# Modulo-1B-TY.net
KiCad netlist of a schematic drawn in Altium Designer
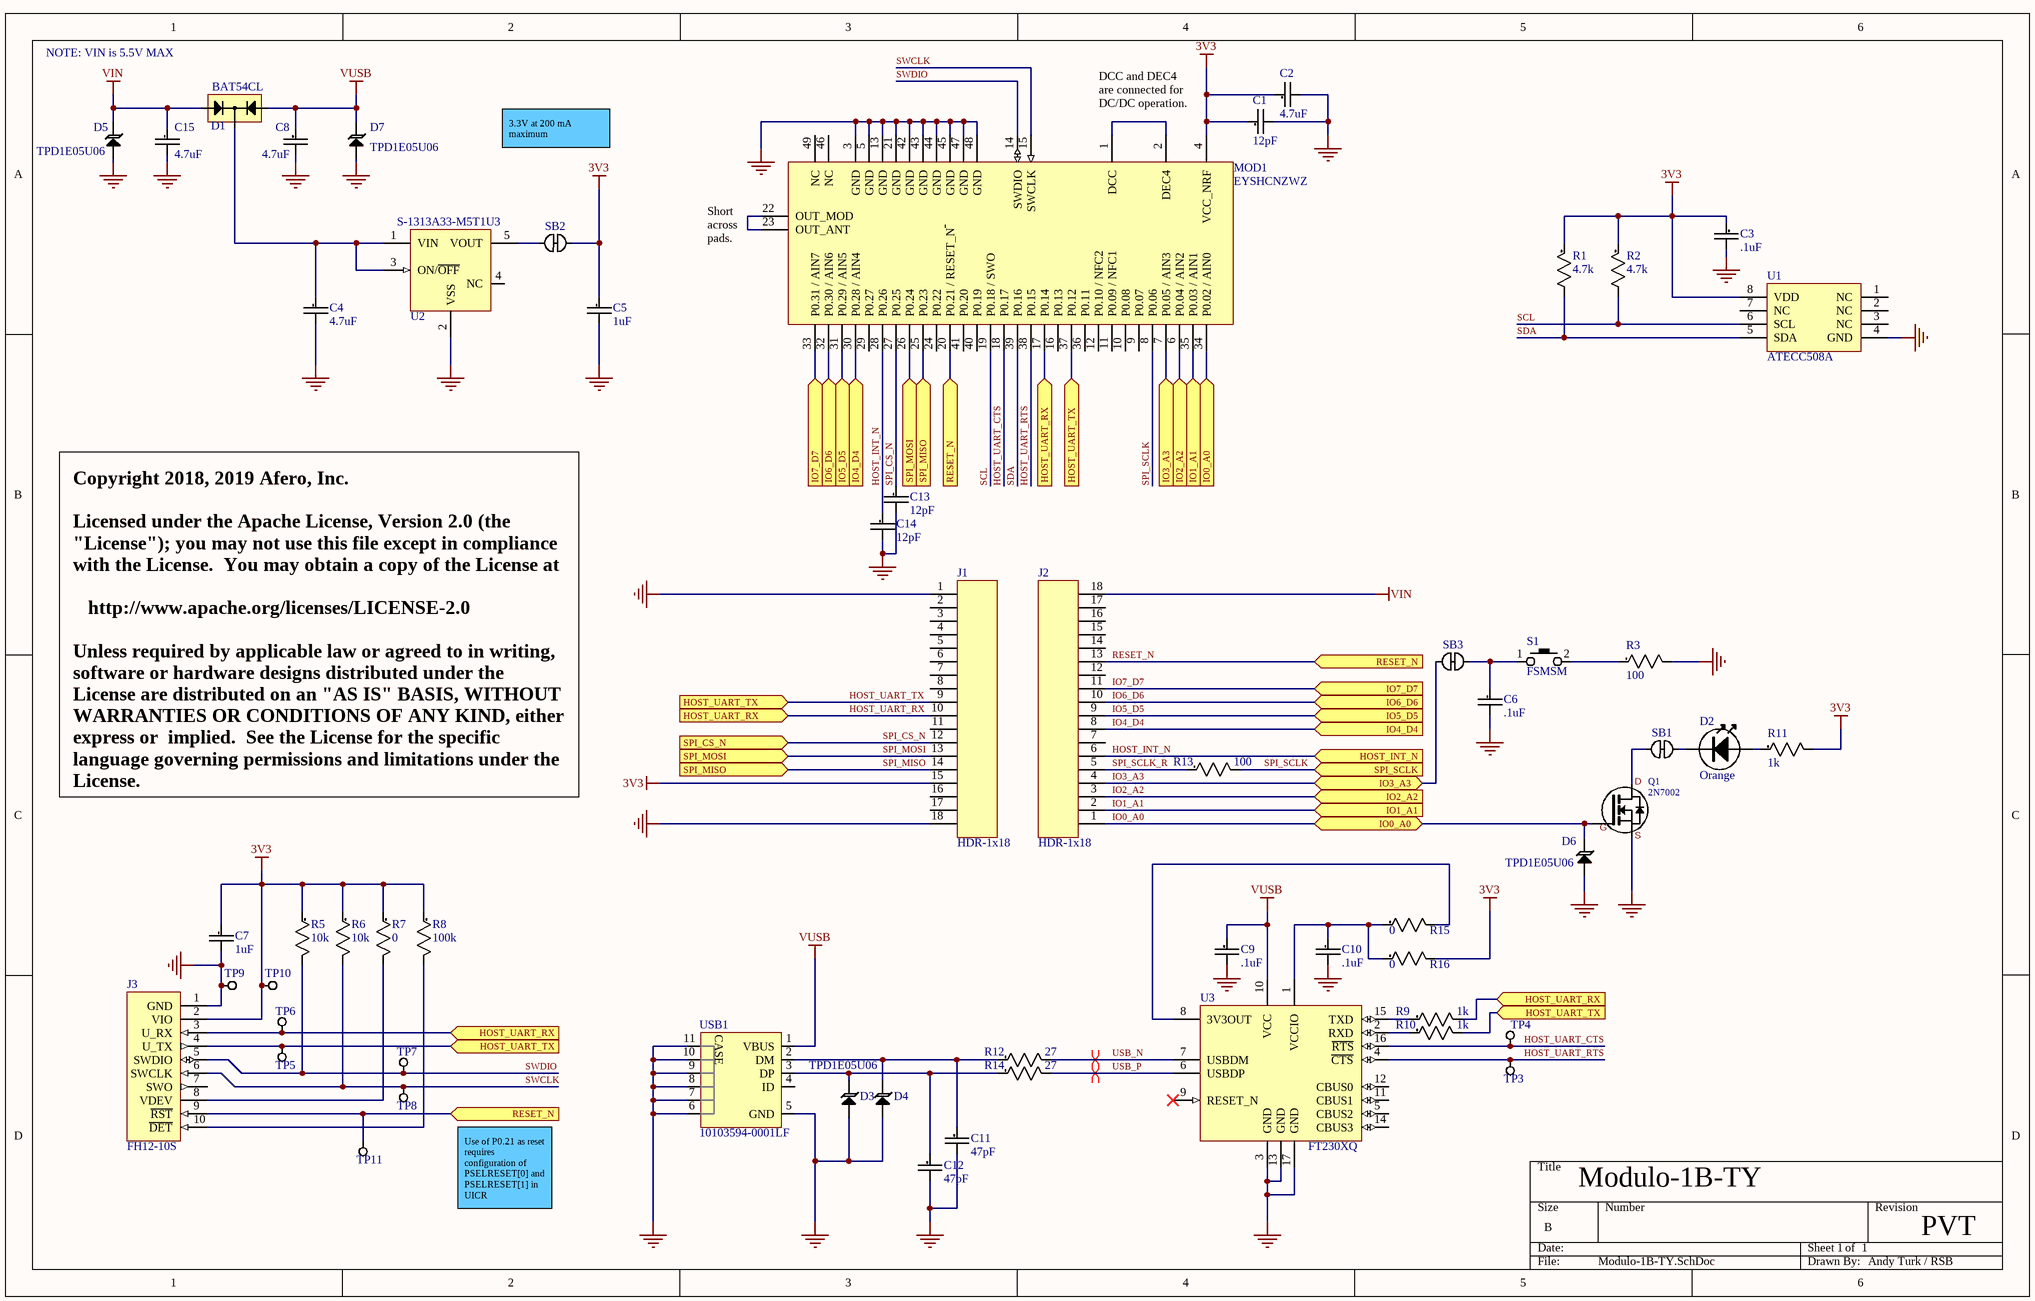
[diagram p0: Modulo-1B-TY.SchDoc]

(export (version "E")
  (design (tool "Eeschema 10.0.6"))
  (components
    (comp (ref "C1")
      (value "12pF")
      (footprint "0402C-GENERIC")
      (description "Capacitor, C0G")
      (fields
        (field (name "MANUFACTURER") "Murata")
        (field (name "MANUFACTURER PART NUMBER") "GJM1555C1H120FB01D")
      )
      (libsource (lib "Modulo-1B-TY") (part "0402C-12p"))
    )
    (comp (ref "C2")
      (value "4.7uF")
      (footprint "0603C-GENERIC")
      (description "Capacitor")
      (fields
        (field (name "MANUFACTURER") "Murata")
        (field (name "MANUFACTURER PART NUMBER") "GRM188R61C475KAAJD")
      )
      (libsource (lib "modulo-1b") (part "0603C-4u7"))
    )
    (comp (ref "C3")
      (value ".1uF")
      (footprint "0402C-GENERIC")
      (description "Capacitor, MLCC")
      (fields
        (field (name "MANUFACTURER") "Murata")
        (field (name "MANUFACTURER PART NUMBER") "GRM155R61H104KE19D")
      )
      (libsource (lib "modulo-1b") (part "0402C-100n"))
    )
    (comp (ref "C4")
      (value "4.7uF")
      (footprint "0603C-GENERIC")
      (description "Capacitor")
      (fields
        (field (name "MANUFACTURER") "Murata")
        (field (name "MANUFACTURER PART NUMBER") "GRM188R61C475KAAJD")
      )
      (libsource (lib "modulo-1b") (part "0603C-4u7"))
    )
    (comp (ref "C5")
      (value "1uF")
      (footprint "0402C-GENERIC")
      (description "Capacitor, MLCC")
      (fields
        (field (name "MANUFACTURER") "Murata Electronics")
        (field (name "MANUFACTURER PART NUMBER") "GRM155R60J105ME19J")
      )
      (libsource (lib "modulo-1b") (part "0402C-1u"))
    )
    (comp (ref "C6")
      (value ".1uF")
      (footprint "0402C-GENERIC")
      (description "Capacitor, MLCC")
      (fields
        (field (name "MANUFACTURER") "Murata")
        (field (name "MANUFACTURER PART NUMBER") "GRM155R61H104KE19D")
      )
      (libsource (lib "modulo-1b") (part "0402C-100n"))
    )
    (comp (ref "C7")
      (value "1uF")
      (footprint "0402C-GENERIC")
      (description "Capacitor, MLCC")
      (fields
        (field (name "MANUFACTURER") "Murata Electronics")
        (field (name "MANUFACTURER PART NUMBER") "GRM155R60J105ME19J")
      )
      (libsource (lib "modulo-1b") (part "0402C-1u"))
    )
    (comp (ref "C8")
      (value "4.7uF")
      (footprint "0603C-GENERIC")
      (description "Capacitor")
      (fields
        (field (name "MANUFACTURER") "Murata")
        (field (name "MANUFACTURER PART NUMBER") "GRM188R61C475KAAJD")
      )
      (libsource (lib "modulo-1b") (part "0603C-4u7"))
    )
    (comp (ref "C9")
      (value ".1uF")
      (footprint "0402C-GENERIC")
      (description "Capacitor, MLCC")
      (fields
        (field (name "MANUFACTURER") "Murata")
        (field (name "MANUFACTURER PART NUMBER") "GRM155R61H104KE19D")
      )
      (libsource (lib "modulo-1b") (part "0402C-100n"))
    )
    (comp (ref "C10")
      (value ".1uF")
      (footprint "0402C-GENERIC")
      (description "Capacitor, MLCC")
      (fields
        (field (name "MANUFACTURER") "Murata")
        (field (name "MANUFACTURER PART NUMBER") "GRM155R61H104KE19D")
      )
      (libsource (lib "modulo-1b") (part "0402C-100n"))
    )
    (comp (ref "C11")
      (value "47pF")
      (footprint "0402C-GENERIC")
      (description "Capacitor, C0G")
      (fields
        (field (name "MANUFACTURER") "Murata")
        (field (name "MANUFACTURER PART NUMBER") "GRM1555C1H470JZ01D")
      )
      (libsource (lib "modulo-1b") (part "0402C-47p"))
    )
    (comp (ref "C12")
      (value "47pF")
      (footprint "0402C-GENERIC")
      (description "Capacitor, C0G")
      (fields
        (field (name "MANUFACTURER") "Murata")
        (field (name "MANUFACTURER PART NUMBER") "GRM1555C1H470JZ01D")
      )
      (libsource (lib "modulo-1b") (part "0402C-47p"))
    )
    (comp (ref "C13")
      (value "12pF")
      (footprint "0402C-GENERIC")
      (description "Capacitor, C0G")
      (fields
        (field (name "MANUFACTURER") "Murata")
        (field (name "MANUFACTURER PART NUMBER") "GJM1555C1H120FB01D")
      )
      (libsource (lib "Modulo-1B-TY") (part "0402C-12p"))
    )
    (comp (ref "C14")
      (value "12pF")
      (footprint "0402C-GENERIC")
      (description "Capacitor, C0G")
      (fields
        (field (name "MANUFACTURER") "Murata")
        (field (name "MANUFACTURER PART NUMBER") "GJM1555C1H120FB01D")
      )
      (libsource (lib "Modulo-1B-TY") (part "0402C-12p"))
    )
    (comp (ref "C15")
      (value "4.7uF")
      (footprint "0603C-GENERIC")
      (description "Capacitor")
      (fields
        (field (name "MANUFACTURER") "Murata")
        (field (name "MANUFACTURER PART NUMBER") "GRM188R61C475KAAJD")
      )
      (libsource (lib "Modulo-1B-TY") (part "0603C-4u7"))
    )
    (comp (ref "D1")
      (value "BAT54CL")
      (footprint "SOT23")
      (description "Dual Common Cathode  Schottky  Diodes")
      (fields
        (field (name "MANUFACTURER") "ON Semiconductor")
        (field (name "MANUFACTURER PART NUMBER") "BAT54CLT1G")
      )
      (libsource (lib "modulo-1b") (part "BAT54CL"))
    )
    (comp (ref "D2")
      (value "Orange")
      (footprint "0603LED")
      (description "LED_0603")
      (fields
        (field (name "MANUFACTURER") "Vishay Lite-On")
        (field (name "MANUFACTURER PART NUMBER") "LTST-C190KAKT")
      )
      (libsource (lib "Modulo-1B-TY") (part "LED_0603"))
    )
    (comp (ref "D3")
      (value "TPD1E05U06")
      (footprint "SON70P100X45-2N")
      (description "TVS Diode")
      (fields
        (field (name "MANUFACTURER") "Texas Instruments")
        (field (name "MANUFACTURER PART NUMBER") "TPD1E05U06DPYR")
      )
      (libsource (lib "modulo-1b") (part "TPD1E05U06"))
    )
    (comp (ref "D4")
      (value "TPD1E05U06")
      (footprint "SON70P100X45-2N")
      (description "TVS Diode")
      (fields
        (field (name "MANUFACTURER") "Texas Instruments")
        (field (name "MANUFACTURER PART NUMBER") "TPD1E05U06DPYR")
      )
      (libsource (lib "modulo-1b") (part "TPD1E05U06"))
    )
    (comp (ref "D5")
      (value "TPD1E05U06")
      (footprint "SON70P100X45-2N")
      (description "TVS Diode")
      (fields
        (field (name "MANUFACTURER") "Texas Instruments")
        (field (name "MANUFACTURER PART NUMBER") "TPD1E05U06DPYR")
      )
      (libsource (lib "Modulo-1B-TY") (part "TPD1E05U06"))
    )
    (comp (ref "D6")
      (value "TPD1E05U06")
      (footprint "SON70P100X45-2N")
      (description "TVS Diode")
      (fields
        (field (name "MANUFACTURER") "Texas Instruments")
        (field (name "MANUFACTURER PART NUMBER") "TPD1E05U06DPYR")
      )
      (libsource (lib "Modulo-1B-TY") (part "TPD1E05U06"))
    )
    (comp (ref "D7")
      (value "TPD1E05U06")
      (footprint "SON70P100X45-2N")
      (description "TVS Diode")
      (fields
        (field (name "MANUFACTURER") "Texas Instruments")
        (field (name "MANUFACTURER PART NUMBER") "TPD1E05U06DPYR")
      )
      (libsource (lib "Modulo-1B-TY") (part "TPD1E05U06"))
    )
    (comp (ref "J1")
      (value "HDR-1x18")
      (footprint "HDR-1X18")
      (libsource (lib "modulo-1b") (part "HDR-1x18"))
    )
    (comp (ref "J2") (value "HDR-1x18") (footprint "HDR-1X18") (libsource (lib "") (part "HDR-1x18_1")))
    (comp (ref "J3")
      (value "FH12-10S")
      (description "Afero SAD connector")
      (fields
        (field (name "MANUFACTURER") "Hirose")
        (field (name "MANUFACTURER PART NUMBER") "FH12-10S-0.5SH(55)")
      )
      (libsource (lib "modulo-1b") (part "SAD-WIFI"))
    )
    (comp (ref "MOD1")
      (value "EYSHCNZWZ")
      (footprint "EYSHCNZWZ")
      (description "Bluetooth 5.0 Low Energy Module")
      (fields (field (name "MANUFACTURER") "Taiyo Yuden"))
      (libsource (lib "modulo-1b") (part "EYSHCNZWZ"))
    )
    (comp (ref "Q1")
      (value "2N7002")
      (footprint "SOT23")
      (description "MOSFET N-CH 60V 115mA SOT23")
      (fields (field (name "MANUFACTURER") "On Semiconductor"))
      (libsource (lib "Modulo-1B-TY") (part "Nch_MOSFET_2N7002"))
    )
    (comp (ref "R1")
      (value "4.7k")
      (footprint "0402R-GENERIC")
      (description "Resistor 4k7")
      (fields
        (field (name "MANUFACTURER") "Panasonic")
        (field (name "MANUFACTURER PART NUMBER") "ERJ-2GEJ472X")
      )
      (libsource (lib "modulo-1b") (part "0402R-4k7"))
    )
    (comp (ref "R2")
      (value "4.7k")
      (footprint "0402R-GENERIC")
      (description "Resistor 4k7")
      (fields
        (field (name "MANUFACTURER") "Panasonic")
        (field (name "MANUFACTURER PART NUMBER") "ERJ-2GEJ472X")
      )
      (libsource (lib "modulo-1b") (part "0402R-4k7"))
    )
    (comp (ref "R3")
      (value "100")
      (footprint "0402R-GENERIC")
      (description "Resistor 100R")
      (fields
        (field (name "MANUFACTURER") "Vishay Dale")
        (field (name "MANUFACTURER PART NUMBER") "CRCW0402100RFKED")
      )
      (libsource (lib "modulo-1b") (part "0402R-100R"))
    )
    (comp (ref "R5")
      (value "10k")
      (footprint "0402R-GENERIC")
      (description "Resistor 10k")
      (fields
        (field (name "MANUFACTURER") "Vishay Dale")
        (field (name "MANUFACTURER PART NUMBER") "CRCW040210K0JNED")
      )
      (libsource (lib "modulo-1b") (part "0402R-10k"))
    )
    (comp (ref "R6")
      (value "10k")
      (footprint "0402R-GENERIC")
      (description "Resistor 10k")
      (fields
        (field (name "MANUFACTURER") "Vishay Dale")
        (field (name "MANUFACTURER PART NUMBER") "CRCW040210K0JNED")
      )
      (libsource (lib "modulo-1b") (part "0402R-10k"))
    )
    (comp (ref "R7")
      (value "0")
      (footprint "0603R-generic")
      (description "Resistor 0R")
      (fields
        (field (name "MANUFACTURER") "Panasonic")
        (field (name "MANUFACTURER PART NUMBER") "ERJ-3GEY0R00V")
      )
      (libsource (lib "modulo-1b") (part "0603R-0R0"))
    )
    (comp (ref "R8")
      (value "100k")
      (footprint "0402R-GENERIC")
      (description "Resistor 100k")
      (fields
        (field (name "MANUFACTURER") "Panasonic")
        (field (name "MANUFACTURER PART NUMBER") "ERJ-2GEJ104X")
      )
      (libsource (lib "modulo-1b") (part "0402R-100k"))
    )
    (comp (ref "R9")
      (value "1k")
      (footprint "0402R-GENERIC")
      (description "Resistor 1k")
      (fields
        (field (name "MANUFACTURER") "Yageo")
        (field (name "MANUFACTURER PART NUMBER") "RT0402-FRE071KL")
      )
      (libsource (lib "modulo-1b") (part "0402R-1k"))
    )
    (comp (ref "R10")
      (value "1k")
      (footprint "0402R-GENERIC")
      (description "Resistor 1k")
      (fields
        (field (name "MANUFACTURER") "Yageo")
        (field (name "MANUFACTURER PART NUMBER") "RT0402-FRE071KL")
      )
      (libsource (lib "modulo-1b") (part "0402R-1k"))
    )
    (comp (ref "R11")
      (value "1k")
      (footprint "0402R-GENERIC")
      (description "Resistor 1k")
      (fields
        (field (name "MANUFACTURER") "Yageo")
        (field (name "MANUFACTURER PART NUMBER") "RT0402-FRE071KL")
      )
      (libsource (lib "Modulo-1B-TY") (part "0402R-1k"))
    )
    (comp (ref "R12")
      (value "27")
      (footprint "0402R-GENERIC")
      (description "Resistor 27R")
      (fields
        (field (name "MANUFACTURER") "Vishay")
        (field (name "MANUFACTURER PART NUMBER") "CRCW040227R0FKED")
      )
      (libsource (lib "modulo-1b") (part "0402R-27R"))
    )
    (comp (ref "R13")
      (value "100")
      (footprint "0402R-GENERIC")
      (description "Resistor 100R")
      (fields
        (field (name "MANUFACTURER") "Vishay Dale")
        (field (name "MANUFACTURER PART NUMBER") "CRCW0402100RFKED")
      )
      (libsource (lib "Modulo-1B-TY") (part "0402R-100R"))
    )
    (comp (ref "R14")
      (value "27")
      (footprint "0402R-GENERIC")
      (description "Resistor 27R")
      (fields
        (field (name "MANUFACTURER") "Vishay")
        (field (name "MANUFACTURER PART NUMBER") "CRCW040227R0FKED")
      )
      (libsource (lib "modulo-1b") (part "0402R-27R"))
    )
    (comp (ref "R15")
      (value "0")
      (footprint "0402R-GENERIC")
      (description "Resistor 0R")
      (fields
        (field (name "MANUFACTURER") "Yageo")
        (field (name "MANUFACTURER PART NUMBER") "RC0402FR-070RL")
      )
      (libsource (lib "Modulo-1B-TY") (part "0402R-0R0"))
    )
    (comp (ref "R16")
      (value "0")
      (footprint "0402R-GENERIC")
      (description "Resistor 0R")
      (fields
        (field (name "MANUFACTURER") "Yageo")
        (field (name "MANUFACTURER PART NUMBER") "RC0402FR-070RL")
      )
      (libsource (lib "Modulo-1B-TY") (part "0402R-0R0"))
    )
    (comp (ref "S1")
      (value "FSMSM")
      (footprint "FSMSM")
      (description "SMD Tact Switch")
      (fields (field (name "MANUFACTURER") "TE Connectivity Alcoswitch"))
      (libsource (lib "modulo-1b") (part "FSMSM"))
    )
    (comp (ref "SB1")
      (value "Solderbridge")
      (footprint "SBNC")
      (description "Solderbridge, Normally Closed")
      (fields
        (field (name "PART NUMBER") "Solderbridge Shorted")
        (field (name "PUBLISHER") "Nordic Semiconductor")
      )
      (libsource (lib "modulo-1c") (part "SBNC"))
    )
    (comp (ref "SB2")
      (value "Solderbridge")
      (footprint "SBNC")
      (description "Solderbridge, Normally Closed")
      (fields
        (field (name "PART NUMBER") "Solderbridge Shorted")
        (field (name "PUBLISHER") "Nordic Semiconductor")
      )
      (libsource (lib "modulo-1c") (part "SBNC"))
    )
    (comp (ref "SB3")
      (value "Solderbridge")
      (footprint "SBNC")
      (description "Solderbridge, Normally Closed")
      (fields
        (field (name "PART NUMBER") "Solderbridge Shorted")
        (field (name "PUBLISHER") "Nordic Semiconductor")
      )
      (libsource (lib "modulo-1c") (part "SBNC"))
    )
    (comp (ref "TP3")
      (value "TP1MM")
      (footprint "TP1MM")
      (description "1mm Test Point")
      (libsource (lib "modulo-1b") (part "TP1MM"))
    )
    (comp (ref "TP4")
      (value "TP1MM")
      (footprint "TP1MM")
      (description "1mm Test Point")
      (libsource (lib "modulo-1b") (part "TP1MM"))
    )
    (comp (ref "TP5")
      (value "TP1MM")
      (footprint "TP1MM")
      (description "1mm Test Point")
      (libsource (lib "modulo-1b") (part "TP1MM"))
    )
    (comp (ref "TP6")
      (value "TP1MM")
      (footprint "TP1MM")
      (description "1mm Test Point")
      (libsource (lib "modulo-1b") (part "TP1MM"))
    )
    (comp (ref "TP7")
      (value "TP1MM")
      (footprint "TP1MM")
      (description "1mm Test Point")
      (libsource (lib "modulo-1b") (part "TP1MM"))
    )
    (comp (ref "TP8")
      (value "TP1MM")
      (footprint "TP1MM")
      (description "1mm Test Point")
      (libsource (lib "modulo-1b") (part "TP1MM"))
    )
    (comp (ref "TP9")
      (value "TP1MM")
      (footprint "TP1MM")
      (description "1mm Test Point")
      (libsource (lib "modulo-1b") (part "TP1MM"))
    )
    (comp (ref "TP10")
      (value "TP1MM")
      (footprint "TP1MM")
      (description "1mm Test Point")
      (libsource (lib "modulo-1b") (part "TP1MM"))
    )
    (comp (ref "TP11")
      (value "TP1MM")
      (footprint "TP1MM")
      (description "1mm Test Point")
      (libsource (lib "modulo-1b") (part "TP1MM"))
    )
    (comp (ref "U1")
      (value "ATECC508A")
      (footprint "SON50P300X60-8N")
      (description "Afero Custom CryptoAuthentication Device")
      (fields
        (field (name "MANUFACTURER") "Microchip / Atmel")
        (field (name "MANUFACTURER PART NUMBER") "ATECC508A-MAHCZ-T")
      )
      (libsource (lib "modulo-1b") (part "ATECC508A"))
    )
    (comp (ref "U2")
      (value "S-1313A33-M5T1U3")
      (footprint "SOT95P275X130-5N")
      (description "Low Current Consumption LDO")
      (fields (field (name "MANUFACTURER") "Seiko"))
      (libsource (lib "modulo-1b") (part "S-1313A33-M5T1U3"))
    )
    (comp (ref "U3")
      (value "FT230XQ")
      (footprint "VQFN65P400X400X90-16N")
      (description "USB to UART Bridge")
      (fields (field (name "MANUFACTURER") "FTDI") (field (name "MANUFACTURER PART NUMBER") "FT230XQ-R"))
      (libsource (lib "modulo-1b") (part "FT230XQ"))
    )
    (comp (ref "USB1")
      (value "10103594-0001LF")
      (footprint "10103594-0001LF")
      (description "MICRO USB B")
      (fields (field (name "MANUFACTURER") "Amphenol FCI"))
      (libsource (lib "modulo-1b") (part "10103594-0001LF"))
    )
  )
  (nets
    (net (code "1") (name "/HOST_INT_N") (class "Default")
      (node (ref "C14") (pin "1") (pintype "passive"))
      (node (ref "J2") (pin "6") (pinfunction "6_6") (pintype "power_in"))
      (node (ref "MOD1") (pin "28") (pinfunction "P0.26_28") (pintype "passive"))
    )
    (net (code "2") (name "/HOST_UART_CTS") (class "Default")
      (node (ref "MOD1") (pin "18") (pinfunction "P0.17_18") (pintype "passive"))
      (node (ref "TP4") (pin "1") (pinfunction "1_1") (pintype "passive"))
      (node (ref "U3") (pin "16") (pinfunction "~{RTS}_16") (pintype "bidirectional"))
    )
    (net (code "3") (name "/HOST_UART_RTS") (class "Default")
      (node (ref "MOD1") (pin "38") (pinfunction "P0.15_38") (pintype "passive"))
      (node (ref "TP3") (pin "1") (pinfunction "1_1") (pintype "passive"))
      (node (ref "U3") (pin "4") (pinfunction "~{CTS}_4") (pintype "bidirectional"))
    )
    (net (code "4") (name "/HOST_UART_RX") (class "Default")
      (node (ref "J1") (pin "10") (pinfunction "10_10") (pintype "passive"))
      (node (ref "J3") (pin "3") (pinfunction "U_RX_3") (pintype "input"))
      (node (ref "MOD1") (pin "17") (pinfunction "P0.14_17") (pintype "passive"))
      (node (ref "R9") (pin "2") (pinfunction "2_2") (pintype "passive"))
      (node (ref "TP6") (pin "1") (pinfunction "1_1") (pintype "passive"))
    )
    (net (code "5") (name "/HOST_UART_TX") (class "Default")
      (node (ref "J1") (pin "9") (pinfunction "9_9") (pintype "passive"))
      (node (ref "J3") (pin "4") (pinfunction "U_TX_4") (pintype "output"))
      (node (ref "MOD1") (pin "37") (pinfunction "P0.12_37") (pintype "passive"))
      (node (ref "R10") (pin "2") (pinfunction "2_2") (pintype "passive"))
      (node (ref "TP5") (pin "1") (pinfunction "1_1") (pintype "passive"))
    )
    (net (code "6") (name "/IO0_A0") (class "Default")
      (node (ref "D6") (pin "1") (pinfunction "I/O_1") (pintype "passive"))
      (node (ref "J2") (pin "1") (pinfunction "1_1") (pintype "power_in"))
      (node (ref "MOD1") (pin "34") (pinfunction "P0.02_/_AIN0_34") (pintype "passive"))
      (node (ref "Q1") (pin "1") (pinfunction "G_1") (pintype "passive"))
    )
    (net (code "7") (name "/IO1_A1") (class "Default")
      (node (ref "J2") (pin "2") (pinfunction "2_2") (pintype "power_in"))
      (node (ref "MOD1") (pin "35") (pinfunction "P0.03_/_AIN1_35") (pintype "passive"))
    )
    (net (code "8") (name "/IO2_A2") (class "Default")
      (node (ref "J2") (pin "3") (pinfunction "3_3") (pintype "power_in"))
      (node (ref "MOD1") (pin "6") (pinfunction "P0.04_/_AIN2_6") (pintype "passive"))
    )
    (net (code "9") (name "/IO3_A3") (class "Default")
      (node (ref "J2") (pin "4") (pinfunction "4_4") (pintype "power_in"))
      (node (ref "MOD1") (pin "7") (pinfunction "P0.05_/_AIN3_7") (pintype "passive"))
      (node (ref "SB3") (pin "1") (pinfunction "0_1") (pintype "passive"))
    )
    (net (code "10") (name "/IO4_D4") (class "Default")
      (node (ref "J2") (pin "8") (pinfunction "8_8") (pintype "power_in"))
      (node (ref "MOD1") (pin "30") (pinfunction "P0.28_/_AIN4_30") (pintype "passive"))
    )
    (net (code "11") (name "/IO5_D5") (class "Default")
      (node (ref "J2") (pin "9") (pinfunction "9_9") (pintype "power_in"))
      (node (ref "MOD1") (pin "31") (pinfunction "P0.29_/_AIN5_31") (pintype "passive"))
    )
    (net (code "12") (name "/IO6_D6") (class "Default")
      (node (ref "J2") (pin "10") (pinfunction "10_10") (pintype "power_in"))
      (node (ref "MOD1") (pin "32") (pinfunction "P0.30_/_AIN6_32") (pintype "passive"))
    )
    (net (code "13") (name "/IO7_D7") (class "Default")
      (node (ref "J2") (pin "11") (pinfunction "11_11") (pintype "power_in"))
      (node (ref "MOD1") (pin "33") (pinfunction "P0.31_/_AIN7_33") (pintype "passive"))
    )
    (net (code "14") (name "/RESET_N") (class "Default")
      (node (ref "J2") (pin "13") (pinfunction "13_13") (pintype "power_in"))
      (node (ref "J3") (pin "9") (pinfunction "~{RST}_9") (pintype "input"))
      (node (ref "MOD1") (pin "20") (pinfunction "P0.21_/_RESET_N~{_}_20") (pintype "passive"))
      (node (ref "TP11") (pin "1") (pinfunction "1_1") (pintype "passive"))
    )
    (net (code "15") (name "/SCL") (class "Default")
      (node (ref "MOD1") (pin "19") (pinfunction "P0.18_/_SWO_19") (pintype "passive"))
      (node (ref "R2") (pin "2") (pinfunction "2_2") (pintype "passive"))
      (node (ref "U1") (pin "6") (pinfunction "SCL_6") (pintype "passive"))
    )
    (net (code "16") (name "/SDA") (class "Default")
      (node (ref "MOD1") (pin "39") (pinfunction "P0.16_39") (pintype "passive"))
      (node (ref "R1") (pin "2") (pinfunction "2_2") (pintype "passive"))
      (node (ref "U1") (pin "5") (pinfunction "SDA_5") (pintype "passive"))
    )
    (net (code "17") (name "/SPI_CS_N") (class "Default")
      (node (ref "C13") (pin "1") (pintype "passive"))
      (node (ref "J1") (pin "12") (pinfunction "12_12") (pintype "passive"))
      (node (ref "MOD1") (pin "27") (pinfunction "P0.25_27") (pintype "passive"))
    )
    (net (code "18") (name "/SPI_MISO") (class "Default")
      (node (ref "J1") (pin "14") (pinfunction "14_14") (pintype "passive"))
      (node (ref "MOD1") (pin "25") (pinfunction "P0.23_25") (pintype "passive"))
    )
    (net (code "19") (name "/SPI_MOSI") (class "Default")
      (node (ref "J1") (pin "13") (pinfunction "13_13") (pintype "passive"))
      (node (ref "MOD1") (pin "26") (pinfunction "P0.24_26") (pintype "passive"))
    )
    (net (code "20") (name "/SPI_SCLK") (class "Default")
      (node (ref "MOD1") (pin "8") (pinfunction "P0.06_8") (pintype "passive"))
      (node (ref "R13") (pin "2") (pinfunction "2_2") (pintype "passive"))
    )
    (net (code "21") (name "/SPI_SCLK_R") (class "Default")
      (node (ref "J2") (pin "5") (pinfunction "5_5") (pintype "power_in"))
      (node (ref "R13") (pin "1") (pinfunction "1_1") (pintype "passive"))
    )
    (net (code "22") (name "/SWCLK") (class "Default")
      (node (ref "J3") (pin "6") (pinfunction "SWCLK_6") (pintype "input"))
      (node (ref "MOD1") (pin "15") (pinfunction "SWCLK_15") (pintype "input"))
      (node (ref "R6") (pin "2") (pinfunction "2_2") (pintype "passive"))
      (node (ref "TP8") (pin "1") (pinfunction "1_1") (pintype "passive"))
    )
    (net (code "23") (name "/SWDIO") (class "Default")
      (node (ref "J3") (pin "5") (pinfunction "SWDIO_5") (pintype "bidirectional"))
      (node (ref "MOD1") (pin "14") (pinfunction "SWDIO_14") (pintype "bidirectional"))
      (node (ref "R5") (pin "2") (pinfunction "2_2") (pintype "passive"))
      (node (ref "TP7") (pin "1") (pinfunction "1_1") (pintype "passive"))
    )
    (net (code "24") (name "/USB_N") (class "Default")
      (node (ref "R12") (pin "2") (pinfunction "2_2") (pintype "passive"))
      (node (ref "U3") (pin "7") (pinfunction "USBDM_7") (pintype "passive"))
    )
    (net (code "25") (name "/USB_P") (class "Default")
      (node (ref "R14") (pin "2") (pinfunction "2_2") (pintype "passive"))
      (node (ref "U3") (pin "6") (pinfunction "USBDP_6") (pintype "passive"))
    )
    (net (code "26") (name "3V3") (class "Default")
      (node (ref "C1") (pin "1") (pintype "passive"))
      (node (ref "C2") (pin "1") (pintype "passive"))
      (node (ref "C3") (pin "1") (pintype "passive"))
      (node (ref "C5") (pin "1") (pintype "passive"))
      (node (ref "C7") (pin "1") (pintype "passive"))
      (node (ref "J1") (pin "15") (pinfunction "15_15") (pintype "passive"))
      (node (ref "J3") (pin "2") (pinfunction "VIO_2") (pintype "power_in"))
      (node (ref "MOD1") (pin "4") (pinfunction "VCC_NRF_4") (pintype "power_in"))
      (node (ref "R1") (pin "1") (pinfunction "1_1") (pintype "passive"))
      (node (ref "R11") (pin "2") (pinfunction "2_2") (pintype "passive"))
      (node (ref "R16") (pin "2") (pinfunction "2_2") (pintype "passive"))
      (node (ref "R2") (pin "1") (pinfunction "1_1") (pintype "passive"))
      (node (ref "R5") (pin "1") (pinfunction "1_1") (pintype "passive"))
      (node (ref "R6") (pin "1") (pinfunction "1_1") (pintype "passive"))
      (node (ref "R7") (pin "1") (pinfunction "1_1") (pintype "passive"))
      (node (ref "R8") (pin "1") (pinfunction "1_1") (pintype "passive"))
      (node (ref "SB2") (pin "2") (pinfunction "1_2") (pintype "passive"))
      (node (ref "TP10") (pin "1") (pinfunction "1_1") (pintype "passive"))
      (node (ref "U1") (pin "8") (pinfunction "VDD_8") (pintype "power_in"))
    )
    (net (code "27") (name "GND") (class "Default")
      (node (ref "C1") (pin "2") (pintype "passive"))
      (node (ref "C10") (pin "2") (pintype "passive"))
      (node (ref "C11") (pin "2") (pintype "passive"))
      (node (ref "C12") (pin "2") (pintype "passive"))
      (node (ref "C13") (pin "2") (pintype "passive"))
      (node (ref "C14") (pin "2") (pintype "passive"))
      (node (ref "C15") (pin "2") (pintype "passive"))
      (node (ref "C2") (pin "2") (pintype "passive"))
      (node (ref "C3") (pin "2") (pintype "passive"))
      (node (ref "C4") (pin "2") (pintype "passive"))
      (node (ref "C5") (pin "2") (pintype "passive"))
      (node (ref "C6") (pin "2") (pintype "passive"))
      (node (ref "C7") (pin "2") (pintype "passive"))
      (node (ref "C8") (pin "2") (pintype "passive"))
      (node (ref "C9") (pin "2") (pintype "passive"))
      (node (ref "D3") (pin "2") (pinfunction "GND_2") (pintype "passive"))
      (node (ref "D4") (pin "2") (pinfunction "GND_2") (pintype "passive"))
      (node (ref "D5") (pin "2") (pinfunction "GND_2") (pintype "passive"))
      (node (ref "D6") (pin "2") (pinfunction "GND_2") (pintype "passive"))
      (node (ref "D7") (pin "2") (pinfunction "GND_2") (pintype "passive"))
      (node (ref "J1") (pin "1") (pinfunction "1_1") (pintype "passive"))
      (node (ref "J1") (pin "18") (pinfunction "18_18") (pintype "passive"))
      (node (ref "J3") (pin "1") (pinfunction "GND_1") (pintype "power_in"))
      (node (ref "MOD1") (pin "13") (pinfunction "GND_13") (pintype "power_in"))
      (node (ref "MOD1") (pin "21") (pinfunction "GND_21") (pintype "power_in"))
      (node (ref "MOD1") (pin "3") (pinfunction "GND_3") (pintype "power_in"))
      (node (ref "MOD1") (pin "42") (pinfunction "GND_42") (pintype "power_in"))
      (node (ref "MOD1") (pin "43") (pinfunction "GND_43") (pintype "power_in"))
      (node (ref "MOD1") (pin "44") (pinfunction "GND_44") (pintype "power_in"))
      (node (ref "MOD1") (pin "45") (pinfunction "GND_45") (pintype "power_in"))
      (node (ref "MOD1") (pin "47") (pinfunction "GND_47") (pintype "power_in"))
      (node (ref "MOD1") (pin "48") (pinfunction "GND_48") (pintype "power_in"))
      (node (ref "MOD1") (pin "5") (pinfunction "GND_5") (pintype "power_in"))
      (node (ref "Q1") (pin "2") (pinfunction "S_2") (pintype "passive"))
      (node (ref "R3") (pin "2") (pinfunction "2_2") (pintype "passive"))
      (node (ref "TP9") (pin "1") (pinfunction "1_1") (pintype "passive"))
      (node (ref "U1") (pin "4") (pinfunction "GND_4") (pintype "power_in"))
      (node (ref "U2") (pin "2") (pinfunction "VSS_2") (pintype "power_in"))
      (node (ref "U3") (pin "13") (pinfunction "GND_13") (pintype "power_in"))
      (node (ref "U3") (pin "17") (pinfunction "GND_17") (pintype "power_in"))
      (node (ref "U3") (pin "3") (pinfunction "GND_3") (pintype "power_in"))
      (node (ref "USB1") (pin "10") (pinfunction "CASE_10") (pintype "passive"))
      (node (ref "USB1") (pin "11") (pinfunction "CASE_11") (pintype "passive"))
      (node (ref "USB1") (pin "5") (pinfunction "GND_5") (pintype "passive"))
      (node (ref "USB1") (pin "6") (pinfunction "CASE_6") (pintype "passive"))
      (node (ref "USB1") (pin "7") (pinfunction "CASE_7") (pintype "passive"))
      (node (ref "USB1") (pin "8") (pinfunction "CASE_8") (pintype "passive"))
      (node (ref "USB1") (pin "9") (pinfunction "CASE_9") (pintype "passive"))
    )
    (net (code "28") (name "Net-(D2-PadA)") (class "Default")
      (node (ref "D2") (pin "A") (pintype "passive"))
      (node (ref "R11") (pin "1") (pinfunction "1_1") (pintype "passive"))
    )
    (net (code "29") (name "Net-(D3-I{slash}O)") (class "Default")
      (node (ref "C12") (pin "1") (pintype "passive"))
      (node (ref "D3") (pin "1") (pinfunction "I/O_1") (pintype "passive"))
      (node (ref "R14") (pin "1") (pinfunction "1_1") (pintype "passive"))
      (node (ref "USB1") (pin "3") (pinfunction "DP_3") (pintype "passive"))
    )
    (net (code "30") (name "Net-(D4-I{slash}O)") (class "Default")
      (node (ref "C11") (pin "1") (pintype "passive"))
      (node (ref "D4") (pin "1") (pinfunction "I/O_1") (pintype "passive"))
      (node (ref "R12") (pin "1") (pinfunction "1_1") (pintype "passive"))
      (node (ref "USB1") (pin "2") (pinfunction "DM_2") (pintype "passive"))
    )
    (net (code "31") (name "Net-(J3-VDEV)") (class "Default")
      (node (ref "J3") (pin "8") (pinfunction "VDEV_8") (pintype "power_in"))
      (node (ref "R7") (pin "2") (pinfunction "2_2") (pintype "passive"))
    )
    (net (code "32") (name "Net-(J3-~{DET})") (class "Default")
      (node (ref "J3") (pin "10") (pinfunction "~{DET}_10") (pintype "input"))
      (node (ref "R8") (pin "2") (pinfunction "2_2") (pintype "passive"))
    )
    (net (code "33") (name "Net-(MOD1-DCC)") (class "Default")
      (node (ref "MOD1") (pin "1") (pinfunction "DCC_1") (pintype "passive"))
      (node (ref "MOD1") (pin "2") (pinfunction "DEC4_2") (pintype "passive"))
    )
    (net (code "34") (name "Net-(MOD1-OUT_ANT)") (class "Default")
      (node (ref "MOD1") (pin "22") (pinfunction "OUT_MOD_22") (pintype "passive"))
      (node (ref "MOD1") (pin "23") (pinfunction "OUT_ANT_23") (pintype "passive"))
    )
    (net (code "35") (name "Net-(Q1-D)") (class "Default")
      (node (ref "Q1") (pin "3") (pinfunction "D_3") (pintype "passive"))
      (node (ref "SB1") (pin "1") (pinfunction "0_1") (pintype "passive"))
    )
    (net (code "36") (name "Net-(R3-Pad1)") (class "Default")
      (node (ref "R3") (pin "1") (pinfunction "1_1") (pintype "passive"))
      (node (ref "S1") (pin "2") (pinfunction "1_2") (pintype "passive"))
    )
    (net (code "37") (name "Net-(SB1-1)") (class "Default")
      (node (ref "D2") (pin "K") (pintype "passive"))
      (node (ref "SB1") (pin "2") (pinfunction "1_2") (pintype "passive"))
    )
    (net (code "38") (name "Net-(SB2-0)") (class "Default")
      (node (ref "SB2") (pin "1") (pinfunction "0_1") (pintype "passive"))
      (node (ref "U2") (pin "5") (pinfunction "VOUT_5") (pintype "power_in"))
    )
    (net (code "39") (name "Net-(SB3-1)") (class "Default")
      (node (ref "C6") (pin "1") (pintype "passive"))
      (node (ref "S1") (pin "1") (pinfunction "1_1") (pintype "passive"))
      (node (ref "SB3") (pin "2") (pinfunction "1_2") (pintype "passive"))
    )
    (net (code "40") (name "Net-(U2-ON{slash}~{OFF})") (class "Default")
      (node (ref "C4") (pin "1") (pintype "passive"))
      (node (ref "D1") (pin "3") (pinfunction "3_3") (pintype "passive"))
      (node (ref "U2") (pin "1") (pinfunction "VIN_1") (pintype "power_in"))
      (node (ref "U2") (pin "3") (pinfunction "ON/~{OFF}_3") (pintype "input"))
    )
    (net (code "41") (name "Net-(U3-3V3OUT)") (class "Default")
      (node (ref "R15") (pin "2") (pinfunction "2_2") (pintype "passive"))
      (node (ref "U3") (pin "8") (pinfunction "3V3OUT_8") (pintype "power_in"))
    )
    (net (code "42") (name "Net-(U3-RXD)") (class "Default")
      (node (ref "R10") (pin "1") (pinfunction "1_1") (pintype "passive"))
      (node (ref "U3") (pin "2") (pinfunction "RXD_2") (pintype "bidirectional"))
    )
    (net (code "43") (name "Net-(U3-TXD)") (class "Default")
      (node (ref "R9") (pin "1") (pinfunction "1_1") (pintype "passive"))
      (node (ref "U3") (pin "15") (pinfunction "TXD_15") (pintype "bidirectional"))
    )
    (net (code "44") (name "Net-(U3-VCCIO)") (class "Default")
      (node (ref "C10") (pin "1") (pintype "passive"))
      (node (ref "R15") (pin "1") (pinfunction "1_1") (pintype "passive"))
      (node (ref "R16") (pin "1") (pinfunction "1_1") (pintype "passive"))
      (node (ref "U3") (pin "1") (pinfunction "VCCIO_1") (pintype "power_in"))
    )
    (net (code "45") (name "VIN") (class "Default")
      (node (ref "C15") (pin "1") (pintype "passive"))
      (node (ref "D1") (pin "1") (pinfunction "1_1") (pintype "passive"))
      (node (ref "D5") (pin "1") (pinfunction "I/O_1") (pintype "passive"))
      (node (ref "J2") (pin "18") (pinfunction "18_18") (pintype "power_in"))
    )
    (net (code "46") (name "VUSB") (class "Default")
      (node (ref "C8") (pin "1") (pintype "passive"))
      (node (ref "C9") (pin "1") (pintype "passive"))
      (node (ref "D1") (pin "2") (pinfunction "2_2") (pintype "passive"))
      (node (ref "D7") (pin "1") (pinfunction "I/O_1") (pintype "passive"))
      (node (ref "U3") (pin "10") (pinfunction "VCC_10") (pintype "power_in"))
      (node (ref "USB1") (pin "1") (pinfunction "VBUS_1") (pintype "passive"))
    )
    (net (code "47") (name "unconnected-(J1-Pad2)") (class "Default")
      (node (ref "J1") (pin "2") (pinfunction "2_2") (pintype "passive"))
    )
    (net (code "48") (name "unconnected-(J1-Pad3)") (class "Default")
      (node (ref "J1") (pin "3") (pinfunction "3_3") (pintype "passive"))
    )
    (net (code "49") (name "unconnected-(J1-Pad4)") (class "Default")
      (node (ref "J1") (pin "4") (pinfunction "4_4") (pintype "passive"))
    )
    (net (code "50") (name "unconnected-(J1-Pad5)") (class "Default")
      (node (ref "J1") (pin "5") (pinfunction "5_5") (pintype "passive"))
    )
    (net (code "51") (name "unconnected-(J1-Pad6)") (class "Default")
      (node (ref "J1") (pin "6") (pinfunction "6_6") (pintype "passive"))
    )
    (net (code "52") (name "unconnected-(J1-Pad7)") (class "Default")
      (node (ref "J1") (pin "7") (pinfunction "7_7") (pintype "passive"))
    )
    (net (code "53") (name "unconnected-(J1-Pad8)") (class "Default")
      (node (ref "J1") (pin "8") (pinfunction "8_8") (pintype "passive"))
    )
    (net (code "54") (name "unconnected-(J1-Pad11)") (class "Default")
      (node (ref "J1") (pin "11") (pinfunction "11_11") (pintype "passive"))
    )
    (net (code "55") (name "unconnected-(J1-Pad16)") (class "Default")
      (node (ref "J1") (pin "16") (pinfunction "16_16") (pintype "passive"))
    )
    (net (code "56") (name "unconnected-(J1-Pad17)") (class "Default")
      (node (ref "J1") (pin "17") (pinfunction "17_17") (pintype "passive"))
    )
    (net (code "57") (name "unconnected-(J2-Pad7)") (class "Default")
      (node (ref "J2") (pin "7") (pinfunction "7_7") (pintype "power_in"))
    )
    (net (code "58") (name "unconnected-(J2-Pad12)") (class "Default")
      (node (ref "J2") (pin "12") (pinfunction "12_12") (pintype "power_in"))
    )
    (net (code "59") (name "unconnected-(J2-Pad14)") (class "Default")
      (node (ref "J2") (pin "14") (pinfunction "14_14") (pintype "power_in"))
    )
    (net (code "60") (name "unconnected-(J2-Pad15)") (class "Default")
      (node (ref "J2") (pin "15") (pinfunction "15_15") (pintype "power_in"))
    )
    (net (code "61") (name "unconnected-(J2-Pad16)") (class "Default")
      (node (ref "J2") (pin "16") (pinfunction "16_16") (pintype "power_in"))
    )
    (net (code "62") (name "unconnected-(J2-Pad17)") (class "Default")
      (node (ref "J2") (pin "17") (pinfunction "17_17") (pintype "power_in"))
    )
    (net (code "63") (name "unconnected-(J3-SWO-Pad7)") (class "Default")
      (node (ref "J3") (pin "7") (pinfunction "SWO_7") (pintype "output"))
    )
    (net (code "64") (name "unconnected-(MOD1-NC-Pad46)") (class "Default")
      (node (ref "MOD1") (pin "46") (pinfunction "NC_46") (pintype "passive"))
    )
    (net (code "65") (name "unconnected-(MOD1-NC-Pad49)") (class "Default")
      (node (ref "MOD1") (pin "49") (pinfunction "NC_49") (pintype "passive"))
    )
    (net (code "66") (name "unconnected-(MOD1-P0.07-Pad9)") (class "Default")
      (node (ref "MOD1") (pin "9") (pinfunction "P0.07_9") (pintype "passive"))
    )
    (net (code "67") (name "unconnected-(MOD1-P0.08-Pad10)") (class "Default")
      (node (ref "MOD1") (pin "10") (pinfunction "P0.08_10") (pintype "passive"))
    )
    (net (code "68") (name "unconnected-(MOD1-P0.09_{slash}_NFC1-Pad11)") (class "Default")
      (node (ref "MOD1") (pin "11") (pinfunction "P0.09_/_NFC1_11") (pintype "passive"))
    )
    (net (code "69") (name "unconnected-(MOD1-P0.10_{slash}_NFC2-Pad12)") (class "Default")
      (node (ref "MOD1") (pin "12") (pinfunction "P0.10_/_NFC2_12") (pintype "passive"))
    )
    (net (code "70") (name "unconnected-(MOD1-P0.11-Pad36)") (class "Default")
      (node (ref "MOD1") (pin "36") (pinfunction "P0.11_36") (pintype "passive"))
    )
    (net (code "71") (name "unconnected-(MOD1-P0.13-Pad16)") (class "Default")
      (node (ref "MOD1") (pin "16") (pinfunction "P0.13_16") (pintype "passive"))
    )
    (net (code "72") (name "unconnected-(MOD1-P0.19-Pad40)") (class "Default")
      (node (ref "MOD1") (pin "40") (pinfunction "P0.19_40") (pintype "passive"))
    )
    (net (code "73") (name "unconnected-(MOD1-P0.20-Pad41)") (class "Default")
      (node (ref "MOD1") (pin "41") (pinfunction "P0.20_41") (pintype "passive"))
    )
    (net (code "74") (name "unconnected-(MOD1-P0.22-Pad24)") (class "Default")
      (node (ref "MOD1") (pin "24") (pinfunction "P0.22_24") (pintype "passive"))
    )
    (net (code "75") (name "unconnected-(MOD1-P0.27-Pad29)") (class "Default")
      (node (ref "MOD1") (pin "29") (pinfunction "P0.27_29") (pintype "passive"))
    )
    (net (code "76") (name "unconnected-(U1-NC-Pad1)") (class "Default")
      (node (ref "U1") (pin "1") (pinfunction "NC_1") (pintype "passive"))
    )
    (net (code "77") (name "unconnected-(U1-NC-Pad2)") (class "Default")
      (node (ref "U1") (pin "2") (pinfunction "NC_2") (pintype "passive"))
    )
    (net (code "78") (name "unconnected-(U1-NC-Pad3)") (class "Default")
      (node (ref "U1") (pin "3") (pinfunction "NC_3") (pintype "passive"))
    )
    (net (code "79") (name "unconnected-(U1-NC-Pad7)") (class "Default")
      (node (ref "U1") (pin "7") (pinfunction "NC_7") (pintype "passive"))
    )
    (net (code "80") (name "unconnected-(U2-NC-Pad4)") (class "Default")
      (node (ref "U2") (pin "4") (pinfunction "NC_4") (pintype "passive"))
    )
    (net (code "81") (name "unconnected-(U3-CBUS0-Pad12)") (class "Default")
      (node (ref "U3") (pin "12") (pinfunction "CBUS0_12") (pintype "bidirectional"))
    )
    (net (code "82") (name "unconnected-(U3-CBUS1-Pad11)") (class "Default")
      (node (ref "U3") (pin "11") (pinfunction "CBUS1_11") (pintype "bidirectional"))
    )
    (net (code "83") (name "unconnected-(U3-CBUS2-Pad5)") (class "Default")
      (node (ref "U3") (pin "5") (pinfunction "CBUS2_5") (pintype "bidirectional"))
    )
    (net (code "84") (name "unconnected-(U3-CBUS3-Pad14)") (class "Default")
      (node (ref "U3") (pin "14") (pinfunction "CBUS3_14") (pintype "bidirectional"))
    )
    (net (code "85") (name "unconnected-(U3-RESET_N-Pad9)") (class "Default")
      (node (ref "U3") (pin "9") (pinfunction "RESET_N_9") (pintype "input+no_connect"))
    )
    (net (code "86") (name "unconnected-(USB1-ID-Pad4)") (class "Default")
      (node (ref "USB1") (pin "4") (pinfunction "ID_4") (pintype "passive"))
    )
  )
)
